# counter-defender-featherwing-mk-1_1.net
KiCad netlist of a schematic drawn in EAGLE
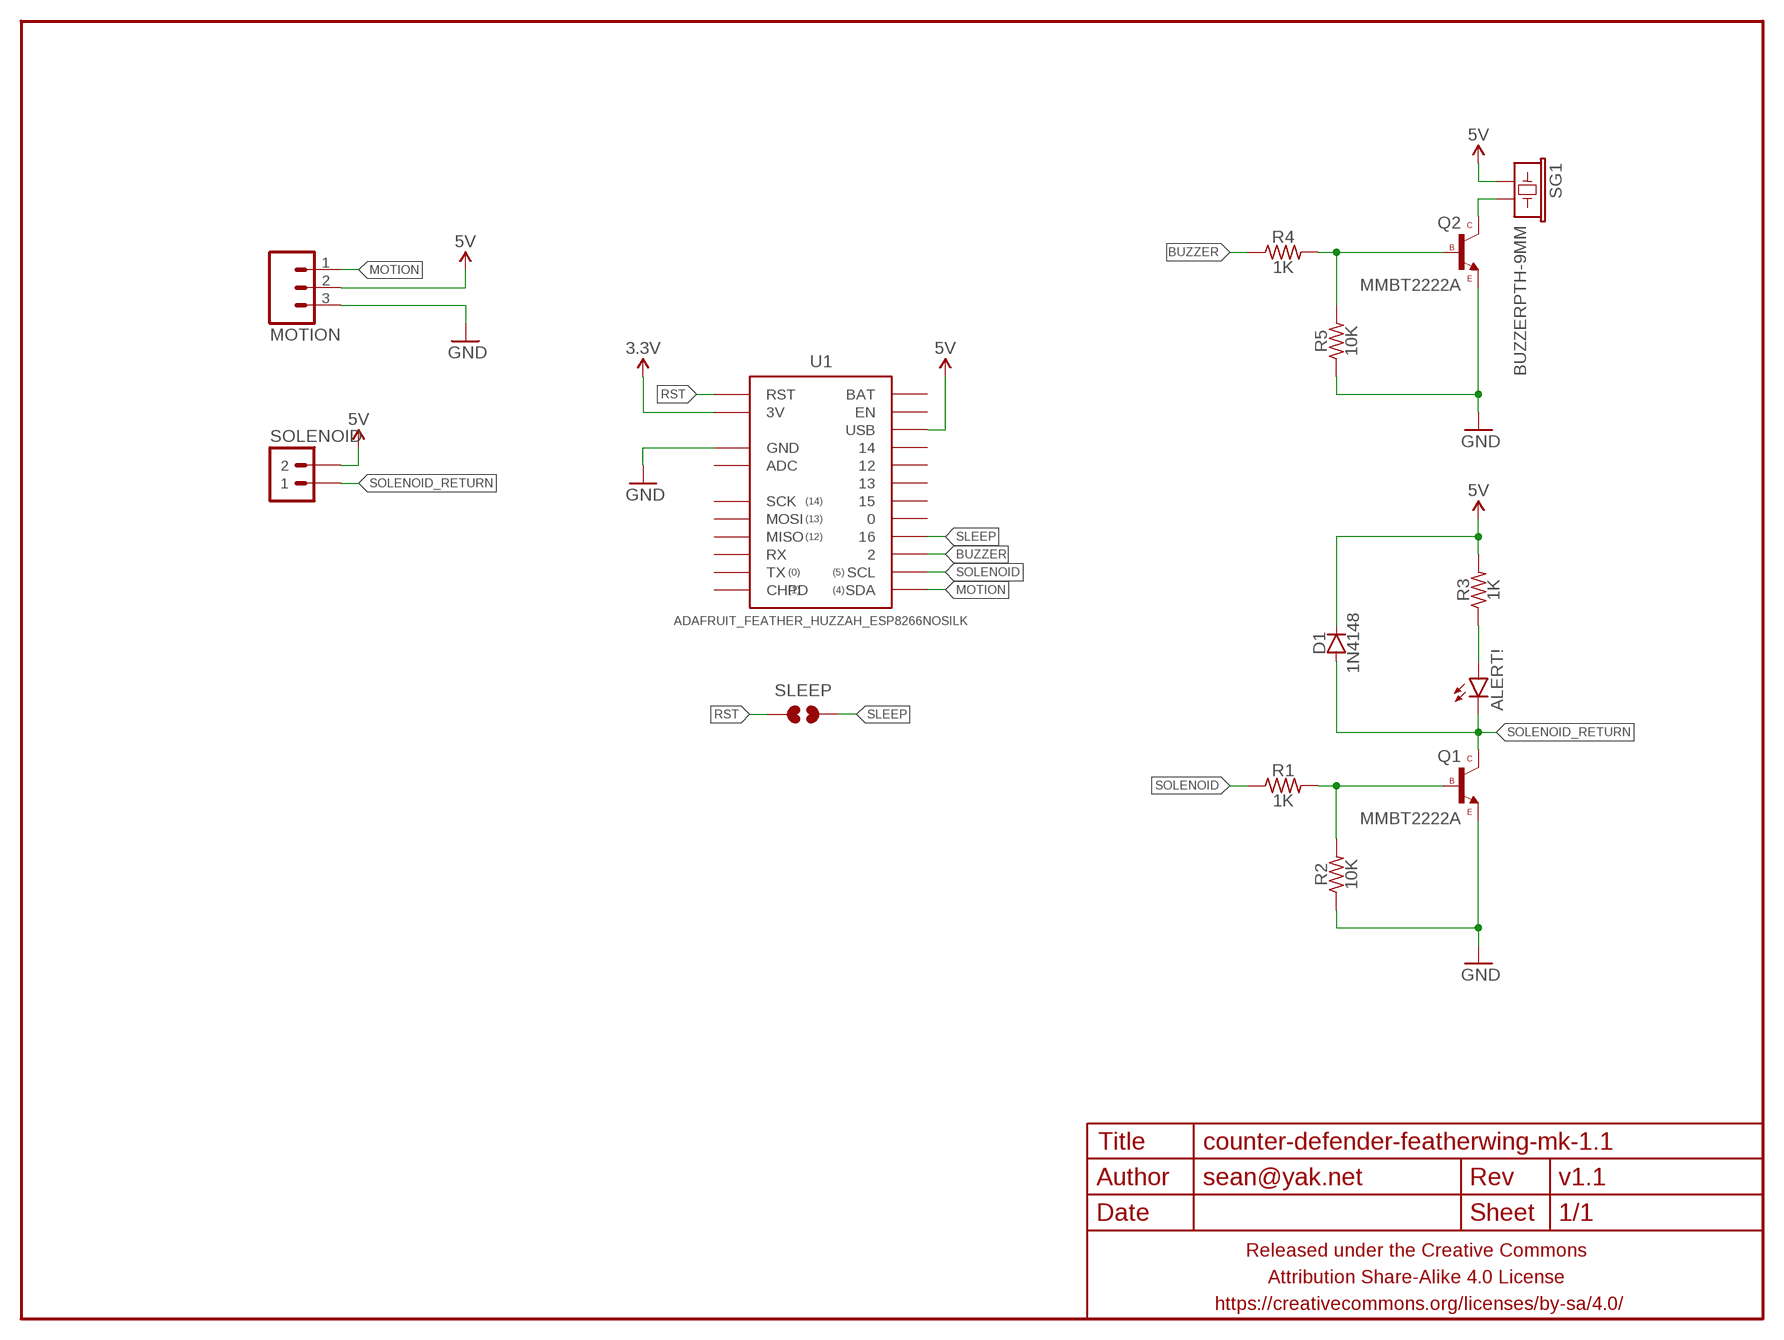
[diagram p0: schematic, sheet 1]

(export (version "E")
  (design (tool "Eeschema 10.0.6"))
  (components
    (comp (ref "ALERT!")
      (value "LED0603-TIGHT")
      (footprint "eagle-import:LED-0603-TIGHT")
      (libsource (lib "eagle-import") (part "LED0603-TIGHT"))
    )
    (comp (ref "D1")
      (value "1N4148")
      (footprint "eagle-import:SOD123")
      (libsource (lib "eagle-import") (part "DIODESOD123"))
    )
    (comp (ref "FRAME1")
      (value "FRAME-LETTERNO_PACKAGE")
      (footprint "eagle-import:DUMMY")
      (fields (field (name "DESIGNER") "sean@yak.net") (field (name "VERSION") "v1.1"))
      (libsource (lib "eagle-import") (part "FRAME-LETTERNO_PACKAGE"))
    )
    (comp (ref "MOTION")
      (value "M03PTH-CENTERED")
      (footprint "eagle-import:1X03-CENTERED")
      (libsource (lib "eagle-import") (part "M03PTH-CENTERED"))
    )
    (comp (ref "Q1")
      (value "MMBT2222A")
      (footprint "eagle-import:SOT23")
      (libsource (lib "eagle-import") (part "TRANSISTOR_NPNMMBT2222A"))
    )
    (comp (ref "Q2")
      (value "MMBT2222A")
      (footprint "eagle-import:SOT23")
      (libsource (lib "eagle-import") (part "TRANSISTOR_NPNMMBT2222A"))
    )
    (comp (ref "R1")
      (value "1K")
      (footprint "eagle-import:R0603-TIGHTER")
      (libsource (lib "eagle-import") (part "RESISTORR0603-TIGHTER"))
    )
    (comp (ref "R2")
      (value "10K")
      (footprint "eagle-import:R0603-TIGHTER")
      (libsource (lib "eagle-import") (part "RESISTORR0603-TIGHTER"))
    )
    (comp (ref "R3")
      (value "1K")
      (footprint "eagle-import:R0603-TIGHTER")
      (libsource (lib "eagle-import") (part "RESISTORR0603-TIGHTER"))
    )
    (comp (ref "R4")
      (value "1K")
      (footprint "eagle-import:R0603-TIGHTER")
      (libsource (lib "eagle-import") (part "RESISTORR0603-TIGHTER"))
    )
    (comp (ref "R5")
      (value "10K")
      (footprint "eagle-import:R0603-TIGHTER")
      (libsource (lib "eagle-import") (part "RESISTORR0603-TIGHTER"))
    )
    (comp (ref "SG1")
      (value "BUZZERPTH-9MM")
      (footprint "eagle-import:BUZZER-PTH-9MM")
      (libsource (lib "eagle-import") (part "BUZZERPTH-9MM"))
    )
    (comp (ref "SLEEP")
      (value "JUMPER-PAD-2-NOYES_SILK")
      (footprint "eagle-import:PAD-JUMPER-2-NO_YES_SILK")
      (libsource (lib "eagle-import") (part "JUMPER-PAD-2-NOYES_SILK"))
    )
    (comp (ref "SOLENOID")
      (value "M02PTH-CENTERED")
      (footprint "eagle-import:1X02-CENTER")
      (libsource (lib "eagle-import") (part "M02PTH-CENTERED"))
    )
    (comp (ref "U1")
      (value "ADAFRUIT_FEATHER_HUZZAH_ESP8266NOSILK")
      (footprint "eagle-import:ADAFRUIT_FEATHER_HUZZAH_NOSILK")
      (libsource (lib "eagle-import") (part "ADAFRUIT_FEATHER_HUZZAH_ESP8266NOSILK"))
    )
  )
  (nets
    (net (code "1") (name "3.3V") (class "Default")
      (node (ref "U1") (pin "3V") (pinfunction "3V_3V") (pintype "bidirectional"))
    )
    (net (code "2") (name "5V") (class "Default")
      (node (ref "D1") (pin "C") (pinfunction "C_C") (pintype "passive"))
      (node (ref "MOTION") (pin "2") (pinfunction "2_2") (pintype "passive"))
      (node (ref "R3") (pin "2") (pinfunction "2_2") (pintype "passive"))
      (node (ref "SG1") (pin "+") (pinfunction "1_+") (pintype "passive"))
      (node (ref "SOLENOID") (pin "2") (pinfunction "2_2") (pintype "passive"))
      (node (ref "U1") (pin "USB") (pinfunction "USB_USB") (pintype "bidirectional"))
    )
    (net (code "3") (name "BUZZER") (class "Default")
      (node (ref "R4") (pin "1") (pinfunction "1_1") (pintype "passive"))
      (node (ref "U1") (pin "2") (pinfunction "2_2") (pintype "bidirectional"))
    )
    (net (code "4") (name "GND") (class "Default")
      (node (ref "MOTION") (pin "3") (pinfunction "3_3") (pintype "passive"))
      (node (ref "Q1") (pin "2") (pinfunction "E_2") (pintype "passive"))
      (node (ref "Q2") (pin "2") (pinfunction "E_2") (pintype "passive"))
      (node (ref "R2") (pin "1") (pinfunction "1_1") (pintype "passive"))
      (node (ref "R5") (pin "1") (pinfunction "1_1") (pintype "passive"))
      (node (ref "U1") (pin "GND@0") (pinfunction "GND_GND@0") (pintype "bidirectional"))
    )
    (net (code "5") (name "MOTION") (class "Default")
      (node (ref "MOTION") (pin "1") (pinfunction "1_1") (pintype "passive"))
      (node (ref "U1") (pin "SDA") (pinfunction "SDA_SDA") (pintype "bidirectional"))
    )
    (net (code "6") (name "Net-(ALERT!-PadA)") (class "Default")
      (node (ref "ALERT!") (pin "A") (pinfunction "A_A") (pintype "passive"))
      (node (ref "R3") (pin "1") (pinfunction "1_1") (pintype "passive"))
    )
    (net (code "7") (name "Net-(Q1-B)") (class "Default")
      (node (ref "Q1") (pin "1") (pinfunction "B_1") (pintype "passive"))
      (node (ref "R1") (pin "2") (pinfunction "2_2") (pintype "passive"))
      (node (ref "R2") (pin "2") (pinfunction "2_2") (pintype "passive"))
    )
    (net (code "8") (name "Net-(Q2-B)") (class "Default")
      (node (ref "Q2") (pin "1") (pinfunction "B_1") (pintype "passive"))
      (node (ref "R4") (pin "2") (pinfunction "2_2") (pintype "passive"))
      (node (ref "R5") (pin "2") (pinfunction "2_2") (pintype "passive"))
    )
    (net (code "9") (name "Net-(Q2-C)") (class "Default")
      (node (ref "Q2") (pin "3") (pinfunction "C_3") (pintype "passive"))
      (node (ref "SG1") (pin "-") (pinfunction "2_-") (pintype "passive"))
    )
    (net (code "10") (name "RST") (class "Default")
      (node (ref "SLEEP") (pin "1") (pinfunction "1_1") (pintype "passive"))
      (node (ref "U1") (pin "RST") (pinfunction "RST_RST") (pintype "bidirectional"))
    )
    (net (code "11") (name "SLEEP") (class "Default")
      (node (ref "SLEEP") (pin "2") (pinfunction "2_2") (pintype "passive"))
      (node (ref "U1") (pin "16") (pinfunction "16_16") (pintype "bidirectional"))
    )
    (net (code "12") (name "SOLENOID") (class "Default")
      (node (ref "R1") (pin "1") (pinfunction "1_1") (pintype "passive"))
      (node (ref "U1") (pin "SCL") (pinfunction "SCL_SCL") (pintype "bidirectional"))
    )
    (net (code "13") (name "SOLENOID_RETURN") (class "Default")
      (node (ref "ALERT!") (pin "C") (pinfunction "C_C") (pintype "passive"))
      (node (ref "D1") (pin "A") (pinfunction "A_A") (pintype "passive"))
      (node (ref "Q1") (pin "3") (pinfunction "C_3") (pintype "passive"))
      (node (ref "SOLENOID") (pin "1") (pinfunction "1_1") (pintype "passive"))
    )
    (net (code "14") (name "unconnected-(U1-Pad0)") (class "Default")
      (node (ref "U1") (pin "0") (pinfunction "0_0") (pintype "bidirectional"))
    )
    (net (code "15") (name "unconnected-(U1-Pad12)") (class "Default")
      (node (ref "U1") (pin "12") (pinfunction "12_12") (pintype "bidirectional"))
    )
    (net (code "16") (name "unconnected-(U1-Pad13)") (class "Default")
      (node (ref "U1") (pin "13") (pinfunction "13_13") (pintype "bidirectional"))
    )
    (net (code "17") (name "unconnected-(U1-Pad14)") (class "Default")
      (node (ref "U1") (pin "14") (pinfunction "14_14") (pintype "bidirectional"))
    )
    (net (code "18") (name "unconnected-(U1-Pad15)") (class "Default")
      (node (ref "U1") (pin "15") (pinfunction "15_15") (pintype "bidirectional"))
    )
    (net (code "19") (name "unconnected-(U1-PadADC)") (class "Default")
      (node (ref "U1") (pin "ADC") (pinfunction "ADC_ADC") (pintype "bidirectional"))
    )
    (net (code "20") (name "unconnected-(U1-PadBAT)") (class "Default")
      (node (ref "U1") (pin "BAT") (pinfunction "BAT_BAT") (pintype "bidirectional"))
    )
    (net (code "21") (name "unconnected-(U1-PadCHPD)") (class "Default")
      (node (ref "U1") (pin "CHPD") (pinfunction "CHPD_CHPD") (pintype "bidirectional"))
    )
    (net (code "22") (name "unconnected-(U1-PadEN)") (class "Default")
      (node (ref "U1") (pin "EN") (pinfunction "EN_EN") (pintype "bidirectional"))
    )
    (net (code "23") (name "unconnected-(U1-PadMISO)") (class "Default")
      (node (ref "U1") (pin "MISO") (pinfunction "MISO_MISO") (pintype "bidirectional"))
    )
    (net (code "24") (name "unconnected-(U1-PadMOSI)") (class "Default")
      (node (ref "U1") (pin "MOSI") (pinfunction "MOSI_MOSI") (pintype "bidirectional"))
    )
    (net (code "25") (name "unconnected-(U1-PadRX)") (class "Default")
      (node (ref "U1") (pin "RX") (pinfunction "RX_RX") (pintype "bidirectional"))
    )
    (net (code "26") (name "unconnected-(U1-PadSCK)") (class "Default")
      (node (ref "U1") (pin "SCK") (pinfunction "SCK_SCK") (pintype "bidirectional"))
    )
    (net (code "27") (name "unconnected-(U1-PadTX)") (class "Default")
      (node (ref "U1") (pin "TX") (pinfunction "TX_TX") (pintype "bidirectional"))
    )
  )
)
